# Ethernet.net
KiCad netlist of a schematic drawn in Altium Designer
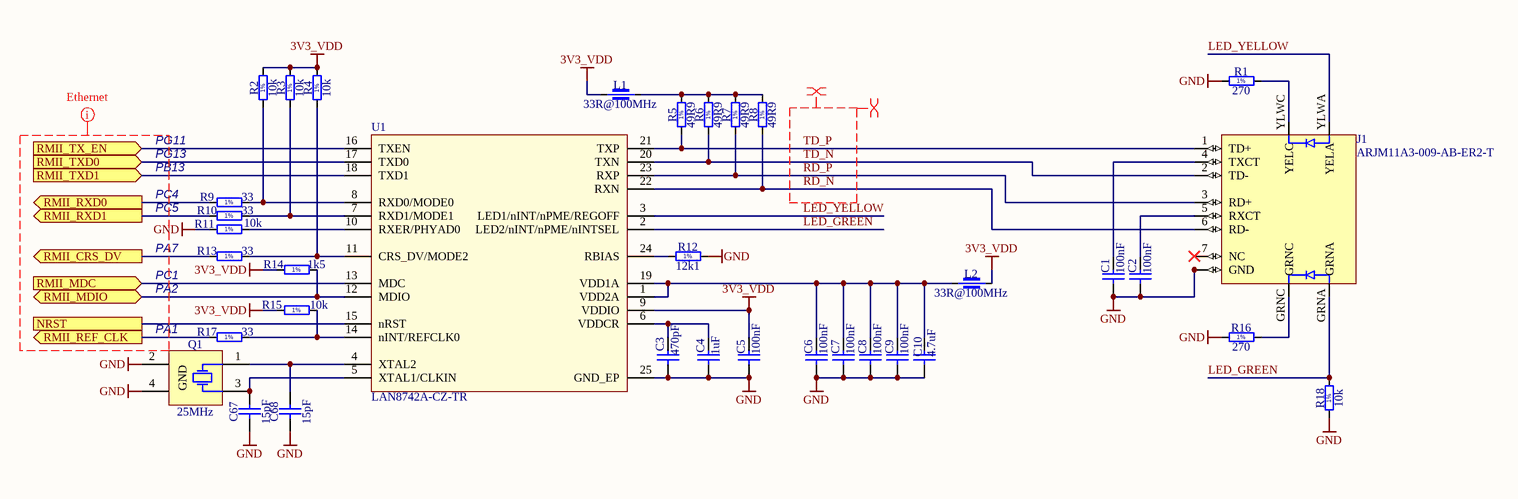
[diagram p0: Ethernet.SchDoc]

(export (version "E")
  (design (tool "Eeschema 10.0.6"))
  (components
    (comp (ref "C1")
      (value "100nF")
      (footprint "CAPC1005X55N")
      (description "Non-polarised capacitor")
      (fields
        (field (name "PART NUMBER") "CC0402_100NF_16V_10%_X7R")
        (field (name "VOLTAGE") "16V")
        (field (name "AUTHOR") "CERN DEM JLC")
      )
      (libsource (lib "Capacitors") (part "Capacitor - non polarized"))
    )
    (comp (ref "C2")
      (value "100nF")
      (footprint "CAPC1005X55N")
      (description "Non-polarised capacitor")
      (fields
        (field (name "PART NUMBER") "CC0402_100NF_16V_10%_X7R")
        (field (name "VOLTAGE") "16V")
        (field (name "AUTHOR") "CERN DEM JLC")
      )
      (libsource (lib "Capacitors") (part "Capacitor - non polarized"))
    )
    (comp (ref "C3")
      (value "470pF")
      (footprint "CAPC1005X55N")
      (description "Non-polarised capacitor")
      (fields
        (field (name "PART NUMBER") "CC0402_470PF_50V_10%_X7R")
        (field (name "VOLTAGE") "50V")
        (field (name "AUTHOR") "CERN DEM JLC")
      )
      (libsource (lib "Capacitors") (part "Capacitor - non polarized"))
    )
    (comp (ref "C4")
      (value "1uF")
      (footprint "CAPC1005X55N")
      (description "Non-polarised capacitor")
      (fields
        (field (name "PART NUMBER") "CC0402_1UF_16V_10%_X5R")
        (field (name "VOLTAGE") "16V")
        (field (name "AUTHOR") "CERN DEM JLC")
      )
      (libsource (lib "Capacitors") (part "Capacitor - non polarized"))
    )
    (comp (ref "C5")
      (value "100nF")
      (footprint "CAPC1005X55N")
      (description "Non-polarised capacitor")
      (fields
        (field (name "PART NUMBER") "CC0402_100NF_16V_10%_X7R")
        (field (name "VOLTAGE") "16V")
        (field (name "AUTHOR") "CERN DEM JLC")
      )
      (libsource (lib "Capacitors") (part "Capacitor - non polarized"))
    )
    (comp (ref "C6")
      (value "100nF")
      (footprint "CAPC1005X55N")
      (description "Non-polarised capacitor")
      (fields
        (field (name "PART NUMBER") "CC0402_100NF_16V_10%_X7R")
        (field (name "VOLTAGE") "16V")
        (field (name "AUTHOR") "CERN DEM JLC")
      )
      (libsource (lib "Capacitors") (part "Capacitor - non polarized"))
    )
    (comp (ref "C7")
      (value "100nF")
      (footprint "CAPC1005X55N")
      (description "Non-polarised capacitor")
      (fields
        (field (name "PART NUMBER") "CC0402_100NF_16V_10%_X7R")
        (field (name "VOLTAGE") "16V")
        (field (name "AUTHOR") "CERN DEM JLC")
      )
      (libsource (lib "Capacitors") (part "Capacitor - non polarized"))
    )
    (comp (ref "C8")
      (value "100nF")
      (footprint "CAPC1005X55N")
      (description "Non-polarised capacitor")
      (fields
        (field (name "PART NUMBER") "CC0402_100NF_16V_10%_X7R")
        (field (name "VOLTAGE") "16V")
        (field (name "AUTHOR") "CERN DEM JLC")
      )
      (libsource (lib "Capacitors") (part "Capacitor - non polarized"))
    )
    (comp (ref "C9")
      (value "100nF")
      (footprint "CAPC1005X55N")
      (description "Non-polarised capacitor")
      (fields
        (field (name "PART NUMBER") "CC0402_100NF_16V_10%_X7R")
        (field (name "VOLTAGE") "16V")
        (field (name "AUTHOR") "CERN DEM JLC")
      )
      (libsource (lib "Capacitors") (part "Capacitor - non polarized"))
    )
    (comp (ref "C10")
      (value "4.7uF")
      (footprint "CAPC1709X95N")
      (description "Non-polarised capacitor")
      (fields
        (field (name "PART NUMBER") "CC0603_4.7UF_16V_10%_X5R")
        (field (name "VOLTAGE") "16V")
        (field (name "AUTHOR") "CERN DEM JLC")
      )
      (libsource (lib "Capacitors") (part "Capacitor - non polarized"))
    )
    (comp (ref "C67")
      (value "15pF")
      (footprint "CAPC1005X55N")
      (description "Non-polarised capacitor")
      (fields
        (field (name "PART NUMBER") "CC0402_15PF_50V_5%_C0G")
        (field (name "VOLTAGE") "50V")
        (field (name "AUTHOR") "CERN DEM JLC")
      )
      (libsource (lib "Capacitors") (part "Capacitor - non polarized"))
    )
    (comp (ref "C68")
      (value "15pF")
      (footprint "CAPC1005X55N")
      (description "Non-polarised capacitor")
      (fields
        (field (name "PART NUMBER") "CC0402_15PF_50V_5%_C0G")
        (field (name "VOLTAGE") "50V")
        (field (name "AUTHOR") "CERN DEM JLC")
      )
      (libsource (lib "Capacitors") (part "Capacitor - non polarized"))
    )
    (comp (ref "J1")
      (value "ARJM11A3-009-AB-ER2-T")
      (footprint "ARJM11A3-009-AB-ER2-T")
      (description "1 Port RJ45 Magjack Connector Through Hole 10/100 Base-T, AutoMDIX")
      (fields (field (name "MF") "Abracon LLC"))
      (libsource (lib "MG_lib") (part "ARJM11A3-009-AB-ER2-T"))
    )
    (comp (ref "L1")
      (value "33R@100MHz")
      (footprint "INDC1005X55N")
      (fields
        (field (name "PART NUMBER") "IND0402_MURATA_BLM15PX330SN1D")
        (field (name "POWER") "3A")
        (field (name "TOLERANCE") "±25%")
        (field (name "AUTHOR") "CERN DEM JMW")
      )
      (libsource (lib "Inductors & Transformers") (part "Ferrite Bead"))
    )
    (comp (ref "L2")
      (value "33R@100MHz")
      (footprint "INDC1005X55N")
      (fields
        (field (name "PART NUMBER") "IND0402_MURATA_BLM15PX330SN1D")
        (field (name "POWER") "3A")
        (field (name "TOLERANCE") "±25%")
        (field (name "AUTHOR") "CERN DEM JMW")
      )
      (libsource (lib "Inductors & Transformers") (part "Ferrite Bead"))
    )
    (comp (ref "Q1")
      (value "25MHz")
      (footprint "XTAL_EPSON_TSX-3225")
      (description "Crystal 4 pins 1=XTAL Control 2=GND3=XTAL 4=GND")
      (fields
        (field (name "PART NUMBER") "XTAL_25MHZ_EPSON_TSX-3225 25.0000MF10Z-AC")
        (field (name "MANUFACTURER") "EPSON")
        (field (name "AUTHOR") "CERN DEM JLC")
      )
      (libsource (lib "ICs And Semiconductors") (part "Quartz Crystal 1X 2GND 3X 4GND"))
    )
    (comp (ref "R1")
      (value "270")
      (footprint "RESC1005X40N")
      (description "Resistor - 1%")
      (fields
        (field (name "PART NUMBER") "R0402_270R_1%_0.0625W_100PPM")
        (field (name "POWER") "0.0625W")
        (field (name "AUTHOR") "CERN DEM JLC")
      )
      (libsource (lib "Resistors") (part "Resistor - 1%"))
    )
    (comp (ref "R2")
      (value "10k")
      (footprint "RESC1005X40N")
      (description "Resistor - 1%")
      (fields
        (field (name "PART NUMBER") "R0402_10K_1%_0.0625W_100PPM")
        (field (name "POWER") "0.0625W")
        (field (name "AUTHOR") "CERN DEM JLC")
      )
      (libsource (lib "Resistors") (part "Resistor - 1%"))
    )
    (comp (ref "R3")
      (value "10k")
      (footprint "RESC1005X40N")
      (description "Resistor - 1%")
      (fields
        (field (name "PART NUMBER") "R0402_10K_1%_0.0625W_100PPM")
        (field (name "POWER") "0.0625W")
        (field (name "AUTHOR") "CERN DEM JLC")
      )
      (libsource (lib "Resistors") (part "Resistor - 1%"))
    )
    (comp (ref "R4")
      (value "10k")
      (footprint "RESC1005X40N")
      (description "Resistor - 1%")
      (fields
        (field (name "PART NUMBER") "R0402_10K_1%_0.0625W_100PPM")
        (field (name "POWER") "0.0625W")
        (field (name "AUTHOR") "CERN DEM JLC")
      )
      (libsource (lib "Resistors") (part "Resistor - 1%"))
    )
    (comp (ref "R5")
      (value "49R9")
      (footprint "RESC1005X40N")
      (description "Resistor - 1%")
      (fields
        (field (name "PART NUMBER") "R0402_49R9_1%_0.0625W_100PPM")
        (field (name "POWER") "0.0625W")
        (field (name "AUTHOR") "CERN DEM JLC")
      )
      (libsource (lib "Resistors") (part "Resistor - 1%"))
    )
    (comp (ref "R6")
      (value "49R9")
      (footprint "RESC1005X40N")
      (description "Resistor - 1%")
      (fields
        (field (name "PART NUMBER") "R0402_49R9_1%_0.0625W_100PPM")
        (field (name "POWER") "0.0625W")
        (field (name "AUTHOR") "CERN DEM JLC")
      )
      (libsource (lib "Resistors") (part "Resistor - 1%"))
    )
    (comp (ref "R7")
      (value "49R9")
      (footprint "RESC1005X40N")
      (description "Resistor - 1%")
      (fields
        (field (name "PART NUMBER") "R0402_49R9_1%_0.0625W_100PPM")
        (field (name "POWER") "0.0625W")
        (field (name "AUTHOR") "CERN DEM JLC")
      )
      (libsource (lib "Resistors") (part "Resistor - 1%"))
    )
    (comp (ref "R8")
      (value "49R9")
      (footprint "RESC1005X40N")
      (description "Resistor - 1%")
      (fields
        (field (name "PART NUMBER") "R0402_49R9_1%_0.0625W_100PPM")
        (field (name "POWER") "0.0625W")
        (field (name "AUTHOR") "CERN DEM JLC")
      )
      (libsource (lib "Resistors") (part "Resistor - 1%"))
    )
    (comp (ref "R9")
      (value "33")
      (footprint "RESC1005X40N")
      (description "Resistor - 1%")
      (fields
        (field (name "PART NUMBER") "R0402_33R_1%_0.0625W_100PPM")
        (field (name "POWER") "0.0625W")
        (field (name "AUTHOR") "CERN DEM JLC")
      )
      (libsource (lib "Resistors") (part "Resistor - 1%"))
    )
    (comp (ref "R10")
      (value "33")
      (footprint "RESC1005X40N")
      (description "Resistor - 1%")
      (fields
        (field (name "PART NUMBER") "R0402_33R_1%_0.0625W_100PPM")
        (field (name "POWER") "0.0625W")
        (field (name "AUTHOR") "CERN DEM JLC")
      )
      (libsource (lib "Resistors") (part "Resistor - 1%"))
    )
    (comp (ref "R11")
      (value "10k")
      (footprint "RESC1005X40N")
      (description "Resistor - 1%")
      (fields
        (field (name "PART NUMBER") "R0402_10K_1%_0.0625W_100PPM")
        (field (name "POWER") "0.0625W")
        (field (name "AUTHOR") "CERN DEM JLC")
      )
      (libsource (lib "Resistors") (part "Resistor - 1%"))
    )
    (comp (ref "R12")
      (value "12k1")
      (footprint "RESC1005X40N")
      (description "Resistor - 1%")
      (fields
        (field (name "PART NUMBER") "R0402_12K1_1%_0.0625W_100PPM")
        (field (name "POWER") "0.0625W")
        (field (name "AUTHOR") "CERN DEM JLC")
      )
      (libsource (lib "Resistors") (part "Resistor - 1%"))
    )
    (comp (ref "R13")
      (value "33")
      (footprint "RESC1005X40N")
      (description "Resistor - 1%")
      (fields
        (field (name "PART NUMBER") "R0402_33R_1%_0.0625W_100PPM")
        (field (name "POWER") "0.0625W")
        (field (name "AUTHOR") "CERN DEM JLC")
      )
      (libsource (lib "Resistors") (part "Resistor - 1%"))
    )
    (comp (ref "R14")
      (value "1k5")
      (footprint "RESC1005X40N")
      (description "Resistor - 1%")
      (fields
        (field (name "PART NUMBER") "R0402_1K5_1%_0.0625W_100PPM")
        (field (name "POWER") "0.0625W")
        (field (name "AUTHOR") "CERN DEM JLC")
      )
      (libsource (lib "Resistors") (part "Resistor - 1%"))
    )
    (comp (ref "R15")
      (value "10k")
      (footprint "RESC1005X40N")
      (description "Resistor - 1%")
      (fields
        (field (name "PART NUMBER") "R0402_10K_1%_0.0625W_100PPM")
        (field (name "POWER") "0.0625W")
        (field (name "AUTHOR") "CERN DEM JLC")
      )
      (libsource (lib "Resistors") (part "Resistor - 1%"))
    )
    (comp (ref "R16")
      (value "270")
      (footprint "RESC1005X40N")
      (description "Resistor - 1%")
      (fields
        (field (name "PART NUMBER") "R0402_270R_1%_0.0625W_100PPM")
        (field (name "POWER") "0.0625W")
        (field (name "AUTHOR") "CERN DEM JLC")
      )
      (libsource (lib "Resistors") (part "Resistor - 1%"))
    )
    (comp (ref "R17")
      (value "33")
      (footprint "RESC1005X40N")
      (description "Resistor - 1%")
      (fields
        (field (name "PART NUMBER") "R0402_33R_1%_0.0625W_100PPM")
        (field (name "POWER") "0.0625W")
        (field (name "AUTHOR") "CERN DEM JLC")
      )
      (libsource (lib "Resistors") (part "Resistor - 1%"))
    )
    (comp (ref "R18")
      (value "10k")
      (footprint "RESC1005X40N")
      (description "Resistor - 1%")
      (fields
        (field (name "PART NUMBER") "R0402_10K_1%_0.0625W_100PPM")
        (field (name "POWER") "0.0625W")
        (field (name "AUTHOR") "CERN DEM JLC")
      )
      (libsource (lib "Resistors") (part "Resistor - 1%"))
    )
    (comp (ref "U1")
      (value "LAN8742A-CZ-TR")
      (footprint "QFN24_0R5_4X4")
      (libsource (lib "MB1137") (part "LAN8742A-CZ-TR"))
    )
  )
  (nets
    (net (code "1") (name "/LED_GREEN") (class "Default")
      (node (ref "J1") (pin "GRNA") (pinfunction "GRNA_GRNA") (pintype "bidirectional"))
      (node (ref "R18") (pin "2") (pinfunction "2_2") (pintype "passive"))
      (node (ref "U1") (pin "2") (pinfunction "LED2/nINT/nPME/nINTSEL_2") (pintype "passive"))
    )
    (net (code "2") (name "/LED_YELLOW") (class "Default")
      (node (ref "J1") (pin "YLWA") (pinfunction "YELA_YLWA") (pintype "bidirectional"))
      (node (ref "U1") (pin "3") (pinfunction "LED1/nINT/nPME/REGOFF_3") (pintype "passive"))
    )
    (net (code "3") (name "/NRST") (class "Default")
      (node (ref "U1") (pin "15") (pinfunction "nRST_15") (pintype "passive"))
    )
    (net (code "4") (name "/RD_N") (class "Default")
      (node (ref "J1") (pin "6") (pinfunction "RD-_6") (pintype "bidirectional"))
      (node (ref "R8") (pin "1") (pinfunction "1_1") (pintype "passive"))
      (node (ref "U1") (pin "22") (pinfunction "RXN_22") (pintype "passive"))
    )
    (net (code "5") (name "/RD_P") (class "Default")
      (node (ref "J1") (pin "3") (pinfunction "RD+_3") (pintype "bidirectional"))
      (node (ref "R7") (pin "1") (pinfunction "1_1") (pintype "passive"))
      (node (ref "U1") (pin "23") (pinfunction "RXP_23") (pintype "passive"))
    )
    (net (code "6") (name "/RMII_CRS_DV") (class "Default")
      (node (ref "R13") (pin "1") (pinfunction "1_1") (pintype "passive"))
    )
    (net (code "7") (name "/RMII_MDC") (class "Default")
      (node (ref "U1") (pin "13") (pinfunction "MDC_13") (pintype "passive"))
    )
    (net (code "8") (name "/RMII_MDIO") (class "Default")
      (node (ref "R14") (pin "2") (pinfunction "2_2") (pintype "passive"))
      (node (ref "U1") (pin "12") (pinfunction "MDIO_12") (pintype "passive"))
    )
    (net (code "9") (name "/RMII_REF_CLK") (class "Default")
      (node (ref "R17") (pin "1") (pinfunction "1_1") (pintype "passive"))
    )
    (net (code "10") (name "/RMII_RXD0") (class "Default")
      (node (ref "R9") (pin "1") (pinfunction "1_1") (pintype "passive"))
    )
    (net (code "11") (name "/RMII_RXD1") (class "Default")
      (node (ref "R10") (pin "1") (pinfunction "1_1") (pintype "passive"))
    )
    (net (code "12") (name "/RMII_TXD0") (class "Default")
      (node (ref "U1") (pin "17") (pinfunction "TXD0_17") (pintype "passive"))
    )
    (net (code "13") (name "/RMII_TXD1") (class "Default")
      (node (ref "U1") (pin "18") (pinfunction "TXD1_18") (pintype "passive"))
    )
    (net (code "14") (name "/RMII_TX_EN") (class "Default")
      (node (ref "U1") (pin "16") (pinfunction "TXEN_16") (pintype "passive"))
    )
    (net (code "15") (name "/TD_N") (class "Default")
      (node (ref "J1") (pin "2") (pinfunction "TD-_2") (pintype "bidirectional"))
      (node (ref "R6") (pin "1") (pinfunction "1_1") (pintype "passive"))
      (node (ref "U1") (pin "20") (pinfunction "TXN_20") (pintype "passive"))
    )
    (net (code "16") (name "/TD_P") (class "Default")
      (node (ref "J1") (pin "1") (pinfunction "TD+_1") (pintype "bidirectional"))
      (node (ref "R5") (pin "1") (pinfunction "1_1") (pintype "passive"))
      (node (ref "U1") (pin "21") (pinfunction "TXP_21") (pintype "passive"))
    )
    (net (code "17") (name "3V3_VDD") (class "Default")
      (node (ref "C5") (pin "2") (pinfunction "2_2") (pintype "passive"))
      (node (ref "L1") (pin "1") (pinfunction "1_1") (pintype "passive"))
      (node (ref "L2") (pin "2") (pinfunction "2_2") (pintype "passive"))
      (node (ref "R14") (pin "1") (pinfunction "1_1") (pintype "passive"))
      (node (ref "R15") (pin "1") (pinfunction "1_1") (pintype "passive"))
      (node (ref "R2") (pin "2") (pinfunction "2_2") (pintype "passive"))
      (node (ref "R3") (pin "2") (pinfunction "2_2") (pintype "passive"))
      (node (ref "R4") (pin "2") (pinfunction "2_2") (pintype "passive"))
      (node (ref "U1") (pin "9") (pinfunction "VDDIO_9") (pintype "passive"))
    )
    (net (code "18") (name "GND") (class "Default")
      (node (ref "C1") (pin "1") (pinfunction "1_1") (pintype "passive"))
      (node (ref "C10") (pin "1") (pinfunction "1_1") (pintype "passive"))
      (node (ref "C2") (pin "1") (pinfunction "1_1") (pintype "passive"))
      (node (ref "C3") (pin "1") (pinfunction "1_1") (pintype "passive"))
      (node (ref "C4") (pin "1") (pinfunction "1_1") (pintype "passive"))
      (node (ref "C5") (pin "1") (pinfunction "1_1") (pintype "passive"))
      (node (ref "C6") (pin "1") (pinfunction "1_1") (pintype "passive"))
      (node (ref "C67") (pin "1") (pinfunction "1_1") (pintype "passive"))
      (node (ref "C68") (pin "1") (pinfunction "1_1") (pintype "passive"))
      (node (ref "C7") (pin "1") (pinfunction "1_1") (pintype "passive"))
      (node (ref "C8") (pin "1") (pinfunction "1_1") (pintype "passive"))
      (node (ref "C9") (pin "1") (pinfunction "1_1") (pintype "passive"))
      (node (ref "J1") (pin "8") (pinfunction "GND_8") (pintype "bidirectional"))
      (node (ref "J1") (pin "P$3") (pinfunction "GND_P$3") (pintype "bidirectional"))
      (node (ref "J1") (pin "P$4") (pinfunction "GND_P$4") (pintype "bidirectional"))
      (node (ref "Q1") (pin "2") (pinfunction "GND_2") (pintype "power_in"))
      (node (ref "Q1") (pin "4") (pinfunction "GND_4") (pintype "power_in"))
      (node (ref "R1") (pin "1") (pinfunction "1_1") (pintype "passive"))
      (node (ref "R11") (pin "1") (pinfunction "1_1") (pintype "passive"))
      (node (ref "R12") (pin "2") (pinfunction "2_2") (pintype "passive"))
      (node (ref "R16") (pin "1") (pinfunction "1_1") (pintype "passive"))
      (node (ref "R18") (pin "1") (pinfunction "1_1") (pintype "passive"))
      (node (ref "U1") (pin "25") (pinfunction "GND_EP_25") (pintype "passive"))
    )
    (net (code "19") (name "Net-(J1-PadGRNC)") (class "Default")
      (node (ref "J1") (pin "GRNC") (pinfunction "GRNC_GRNC") (pintype "bidirectional"))
      (node (ref "R16") (pin "2") (pinfunction "2_2") (pintype "passive"))
    )
    (net (code "20") (name "Net-(J1-RXCT)") (class "Default")
      (node (ref "C2") (pin "2") (pinfunction "2_2") (pintype "passive"))
      (node (ref "J1") (pin "5") (pinfunction "RXCT_5") (pintype "bidirectional"))
    )
    (net (code "21") (name "Net-(J1-TXCT)") (class "Default")
      (node (ref "C1") (pin "2") (pinfunction "2_2") (pintype "passive"))
      (node (ref "J1") (pin "4") (pinfunction "TXCT_4") (pintype "bidirectional"))
    )
    (net (code "22") (name "Net-(J1-YELC)") (class "Default")
      (node (ref "J1") (pin "YLWC") (pinfunction "YELC_YLWC") (pintype "bidirectional"))
      (node (ref "R1") (pin "2") (pinfunction "2_2") (pintype "passive"))
    )
    (net (code "23") (name "Net-(L1-Pad2)") (class "Default")
      (node (ref "L1") (pin "2") (pinfunction "2_2") (pintype "passive"))
      (node (ref "R5") (pin "2") (pinfunction "2_2") (pintype "passive"))
      (node (ref "R6") (pin "2") (pinfunction "2_2") (pintype "passive"))
      (node (ref "R7") (pin "2") (pinfunction "2_2") (pintype "passive"))
      (node (ref "R8") (pin "2") (pinfunction "2_2") (pintype "passive"))
    )
    (net (code "24") (name "Net-(U1-CRS_DV{slash}MODE2)") (class "Default")
      (node (ref "R13") (pin "2") (pinfunction "2_2") (pintype "passive"))
      (node (ref "R4") (pin "1") (pinfunction "1_1") (pintype "passive"))
      (node (ref "U1") (pin "11") (pinfunction "CRS_DV/MODE2_11") (pintype "passive"))
    )
    (net (code "25") (name "Net-(U1-RBIAS)") (class "Default")
      (node (ref "R12") (pin "1") (pinfunction "1_1") (pintype "passive"))
      (node (ref "U1") (pin "24") (pinfunction "RBIAS_24") (pintype "passive"))
    )
    (net (code "26") (name "Net-(U1-RXD0{slash}MODE0)") (class "Default")
      (node (ref "R2") (pin "1") (pinfunction "1_1") (pintype "passive"))
      (node (ref "R9") (pin "2") (pinfunction "2_2") (pintype "passive"))
      (node (ref "U1") (pin "8") (pinfunction "RXD0/MODE0_8") (pintype "passive"))
    )
    (net (code "27") (name "Net-(U1-RXD1{slash}MODE1)") (class "Default")
      (node (ref "R10") (pin "2") (pinfunction "2_2") (pintype "passive"))
      (node (ref "R3") (pin "1") (pinfunction "1_1") (pintype "passive"))
      (node (ref "U1") (pin "7") (pinfunction "RXD1/MODE1_7") (pintype "passive"))
    )
    (net (code "28") (name "Net-(U1-RXER{slash}PHYAD0)") (class "Default")
      (node (ref "R11") (pin "2") (pinfunction "2_2") (pintype "passive"))
      (node (ref "U1") (pin "10") (pinfunction "RXER/PHYAD0_10") (pintype "passive"))
    )
    (net (code "29") (name "Net-(U1-VDD1A)") (class "Default")
      (node (ref "C10") (pin "2") (pinfunction "2_2") (pintype "passive"))
      (node (ref "C6") (pin "2") (pinfunction "2_2") (pintype "passive"))
      (node (ref "C7") (pin "2") (pinfunction "2_2") (pintype "passive"))
      (node (ref "C8") (pin "2") (pinfunction "2_2") (pintype "passive"))
      (node (ref "C9") (pin "2") (pinfunction "2_2") (pintype "passive"))
      (node (ref "L2") (pin "1") (pinfunction "1_1") (pintype "passive"))
      (node (ref "U1") (pin "1") (pinfunction "VDD2A_1") (pintype "passive"))
      (node (ref "U1") (pin "19") (pinfunction "VDD1A_19") (pintype "passive"))
    )
    (net (code "30") (name "Net-(U1-VDDCR)") (class "Default")
      (node (ref "C3") (pin "2") (pinfunction "2_2") (pintype "passive"))
      (node (ref "C4") (pin "2") (pinfunction "2_2") (pintype "passive"))
      (node (ref "U1") (pin "6") (pinfunction "VDDCR_6") (pintype "passive"))
    )
    (net (code "31") (name "Net-(U1-XTAL1{slash}CLKIN)") (class "Default")
      (node (ref "C67") (pin "2") (pinfunction "2_2") (pintype "passive"))
      (node (ref "Q1") (pin "3") (pinfunction "X_3") (pintype "passive"))
      (node (ref "U1") (pin "5") (pinfunction "XTAL1/CLKIN_5") (pintype "passive"))
    )
    (net (code "32") (name "Net-(U1-XTAL2)") (class "Default")
      (node (ref "C68") (pin "2") (pinfunction "2_2") (pintype "passive"))
      (node (ref "Q1") (pin "1") (pinfunction "X_1") (pintype "passive"))
      (node (ref "U1") (pin "4") (pinfunction "XTAL2_4") (pintype "passive"))
    )
    (net (code "33") (name "Net-(U1-nINT{slash}REFCLK0)") (class "Default")
      (node (ref "R15") (pin "2") (pinfunction "2_2") (pintype "passive"))
      (node (ref "R17") (pin "2") (pinfunction "2_2") (pintype "passive"))
      (node (ref "U1") (pin "14") (pinfunction "nINT/REFCLK0_14") (pintype "passive"))
    )
    (net (code "34") (name "unconnected-(J1-NC-Pad7)") (class "Default")
      (node (ref "J1") (pin "7") (pinfunction "NC_7") (pintype "bidirectional+no_connect"))
    )
  )
)
